# fet-adapter.net
KiCad netlist of a schematic drawn in Altium Designer
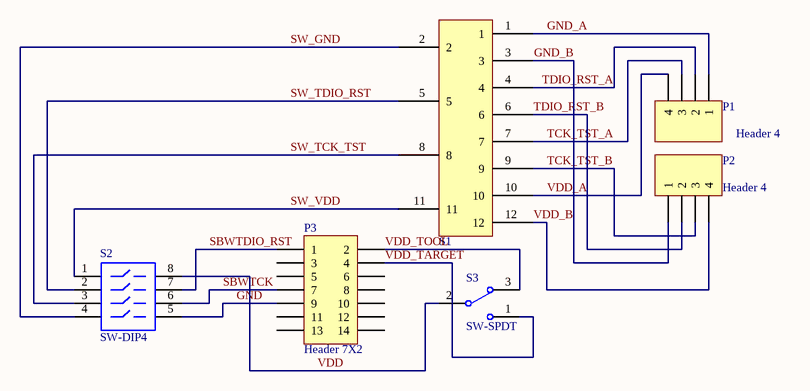
[diagram p0: fet-adapter.SchDoc]

(export (version "E")
  (design (tool "Eeschema 10.0.6"))
  (components
    (comp (ref "P1")
      (value "Header 4")
      (footprint "HDR1X4")
      (description "Header, 4-Pin")
      (fields (field (name "PUBLISHER") "Altium Limited"))
      (libsource (lib "") (part "Header 4_1"))
    )
    (comp (ref "P2")
      (value "Header 4")
      (footprint "HDR1X4")
      (description "Header, 4-Pin")
      (fields (field (name "PUBLISHER") "Altium Limited"))
      (libsource (lib "Miscellaneous Connectors") (part "Header 4"))
    )
    (comp (ref "P3")
      (value "Header 7X2")
      (footprint "JTAG-14PIN")
      (description "Header, 7-Pin, Dual row")
      (fields
        (field (name "DISTRIBUTORPARTNUMBER") "ED10522-ND")
        (field (name "MANUFACTURER") "On Shore Technology Inc.")
      )
      (libsource (lib "Miscellaneous Connectors") (part "Header 7X2"))
    )
    (comp (ref "S1")
      (value "4PDT")
      (footprint "MFS401N2Z")
      (description "4PDT Switch")
      (fields
        (field (name "MANUFACTURERPARTNUMBER") "MFS401N-2-Z")
        (field (name "MANUFACTURER") "Copal Electronics")
      )
      (libsource (lib "Lib") (part "SW_4PDT"))
    )
    (comp (ref "S2")
      (value "SW-DIP4")
      (footprint "DIP4PST")
      (description "DIP Switch")
      (fields
        (field (name "DISTRIBUTORPARTNUMBER") "GH7198-ND")
        (field (name "MANUFACTURER") "Grayhill Inc.")
      )
      (libsource (lib "Miscellaneous Devices") (part "SW-DIP4"))
    )
    (comp (ref "S3")
      (value "SW-SPDT")
      (footprint "MFS101D15Z")
      (description "SPDT Subminiature Toggle Switch, Right Angle Mounting, Vertical Actuation")
      (fields
        (field (name "DISTRIBUTORPARTNUMBER") "563-1554-ND")
        (field (name "MANUFACTURER") "Copal Electronics")
      )
      (libsource (lib "Miscellaneous Devices") (part "SW-SPDT"))
    )
  )
  (nets
    (net (code "1") (name "/GND") (class "Default")
      (node (ref "P3") (pin "9") (pinfunction "9_9") (pintype "passive"))
      (node (ref "S2") (pin "5") (pinfunction "5_5") (pintype "passive"))
    )
    (net (code "2") (name "/GND_A") (class "Default")
      (node (ref "P1") (pin "1") (pinfunction "1_1") (pintype "passive"))
      (node (ref "S1") (pin "1") (pinfunction "1_1") (pintype "passive"))
    )
    (net (code "3") (name "/GND_B") (class "Default")
      (node (ref "P2") (pin "1") (pinfunction "1_1") (pintype "passive"))
      (node (ref "S1") (pin "3") (pinfunction "3_3") (pintype "passive"))
    )
    (net (code "4") (name "/SBWTCK") (class "Default")
      (node (ref "P3") (pin "7") (pinfunction "7_7") (pintype "passive"))
      (node (ref "S2") (pin "6") (pinfunction "6_6") (pintype "passive"))
    )
    (net (code "5") (name "/SBWTDIO_RST") (class "Default")
      (node (ref "P3") (pin "1") (pinfunction "1_1") (pintype "passive"))
      (node (ref "S2") (pin "7") (pinfunction "7_7") (pintype "passive"))
    )
    (net (code "6") (name "/SW_GND") (class "Default")
      (node (ref "S1") (pin "2") (pinfunction "2_2") (pintype "passive"))
      (node (ref "S2") (pin "4") (pinfunction "4_4") (pintype "passive"))
    )
    (net (code "7") (name "/SW_TCK_TST") (class "Default")
      (node (ref "S1") (pin "8") (pinfunction "8_8") (pintype "passive"))
      (node (ref "S2") (pin "3") (pinfunction "3_3") (pintype "passive"))
    )
    (net (code "8") (name "/SW_TDIO_RST") (class "Default")
      (node (ref "S1") (pin "5") (pinfunction "5_5") (pintype "passive"))
      (node (ref "S2") (pin "2") (pinfunction "2_2") (pintype "passive"))
    )
    (net (code "9") (name "/SW_VDD") (class "Default")
      (node (ref "S1") (pin "11") (pinfunction "11_11") (pintype "passive"))
      (node (ref "S2") (pin "1") (pinfunction "1_1") (pintype "passive"))
    )
    (net (code "10") (name "/TCK_TST_A") (class "Default")
      (node (ref "P1") (pin "3") (pinfunction "3_3") (pintype "passive"))
      (node (ref "S1") (pin "7") (pinfunction "7_7") (pintype "passive"))
    )
    (net (code "11") (name "/TCK_TST_B") (class "Default")
      (node (ref "P2") (pin "3") (pinfunction "3_3") (pintype "passive"))
      (node (ref "S1") (pin "9") (pinfunction "9_9") (pintype "passive"))
    )
    (net (code "12") (name "/TDIO_RST_A") (class "Default")
      (node (ref "P1") (pin "2") (pinfunction "2_2") (pintype "passive"))
      (node (ref "S1") (pin "4") (pinfunction "4_4") (pintype "passive"))
    )
    (net (code "13") (name "/TDIO_RST_B") (class "Default")
      (node (ref "P2") (pin "2") (pinfunction "2_2") (pintype "passive"))
      (node (ref "S1") (pin "6") (pinfunction "6_6") (pintype "passive"))
    )
    (net (code "14") (name "/VDD") (class "Default")
      (node (ref "S2") (pin "8") (pinfunction "8_8") (pintype "passive"))
      (node (ref "S3") (pin "2") (pinfunction "2_2") (pintype "passive"))
    )
    (net (code "15") (name "/VDD_A") (class "Default")
      (node (ref "P1") (pin "4") (pinfunction "4_4") (pintype "passive"))
      (node (ref "S1") (pin "10") (pinfunction "10_10") (pintype "passive"))
    )
    (net (code "16") (name "/VDD_B") (class "Default")
      (node (ref "P2") (pin "4") (pinfunction "4_4") (pintype "passive"))
      (node (ref "S1") (pin "12") (pinfunction "12_12") (pintype "passive"))
    )
    (net (code "17") (name "/VDD_TARGET") (class "Default")
      (node (ref "P3") (pin "4") (pinfunction "4_4") (pintype "passive"))
      (node (ref "S3") (pin "1") (pinfunction "1_1") (pintype "passive"))
    )
    (net (code "18") (name "/VDD_TOOL") (class "Default")
      (node (ref "P3") (pin "2") (pinfunction "2_2") (pintype "passive"))
      (node (ref "S3") (pin "3") (pinfunction "3_3") (pintype "passive"))
    )
    (net (code "19") (name "unconnected-(P3-Pad3)") (class "Default")
      (node (ref "P3") (pin "3") (pinfunction "3_3") (pintype "passive"))
    )
    (net (code "20") (name "unconnected-(P3-Pad5)") (class "Default")
      (node (ref "P3") (pin "5") (pinfunction "5_5") (pintype "passive"))
    )
    (net (code "21") (name "unconnected-(P3-Pad6)") (class "Default")
      (node (ref "P3") (pin "6") (pinfunction "6_6") (pintype "passive"))
    )
    (net (code "22") (name "unconnected-(P3-Pad8)") (class "Default")
      (node (ref "P3") (pin "8") (pinfunction "8_8") (pintype "passive"))
    )
    (net (code "23") (name "unconnected-(P3-Pad10)") (class "Default")
      (node (ref "P3") (pin "10") (pinfunction "10_10") (pintype "passive"))
    )
    (net (code "24") (name "unconnected-(P3-Pad11)") (class "Default")
      (node (ref "P3") (pin "11") (pinfunction "11_11") (pintype "passive"))
    )
    (net (code "25") (name "unconnected-(P3-Pad12)") (class "Default")
      (node (ref "P3") (pin "12") (pinfunction "12_12") (pintype "passive"))
    )
    (net (code "26") (name "unconnected-(P3-Pad13)") (class "Default")
      (node (ref "P3") (pin "13") (pinfunction "13_13") (pintype "passive"))
    )
    (net (code "27") (name "unconnected-(P3-Pad14)") (class "Default")
      (node (ref "P3") (pin "14") (pinfunction "14_14") (pintype "passive"))
    )
  )
)
